# easyServo_easyEDA_PRO.net
KiCad netlist of a schematic drawn in EasyEDA Pro
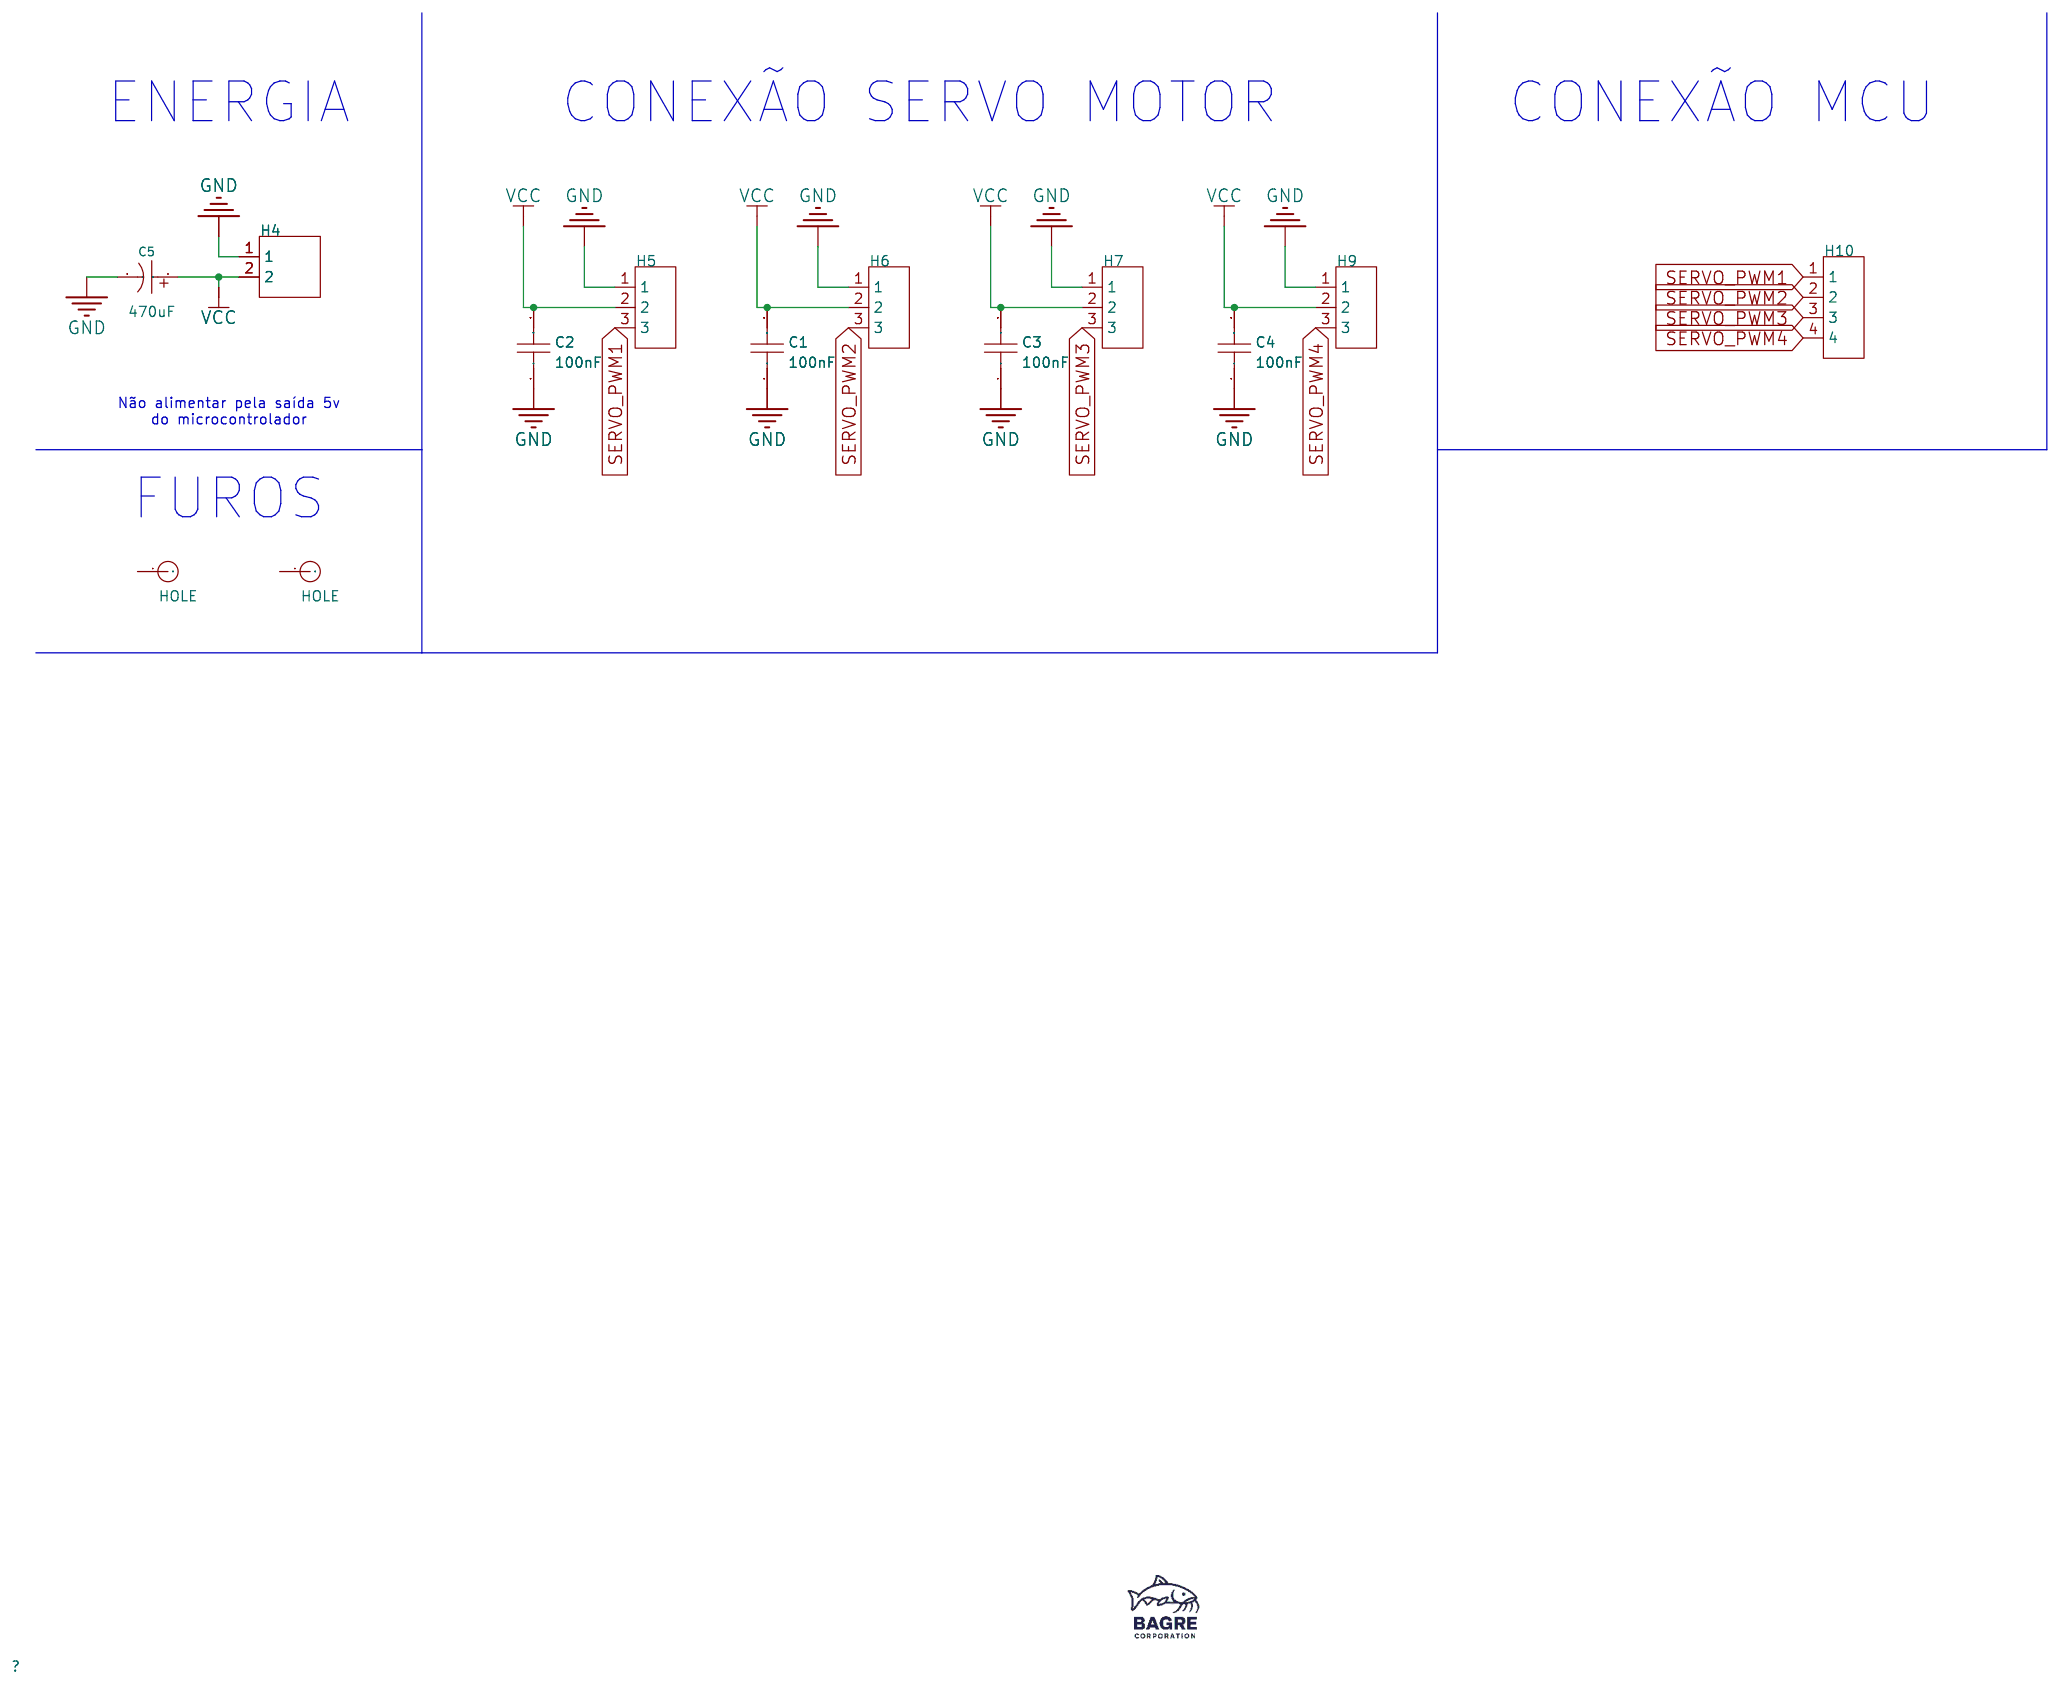
[diagram p0: schematic sheet]

(export (version "E")
  (design (tool "Eeschema 10.0.6"))
  (components
    (comp (ref "C1")
      (value "100nF")
      (footprint "easyedapro:C1206")
      (fields (field (name "Manufacturer Part") "CGJ5L3X7R2D104K160AA") (field (name "Manufacturer") "TDK"))
      (libsource (lib "easyedapro") (part "CGJ5L3X7R2D104K160AA_C3883443"))
    )
    (comp (ref "C2")
      (value "100nF")
      (footprint "easyedapro:C1206")
      (fields (field (name "Manufacturer Part") "CGJ5L3X7R2D104K160AA") (field (name "Manufacturer") "TDK"))
      (libsource (lib "easyedapro") (part "CGJ5L3X7R2D104K160AA_C3883443"))
    )
    (comp (ref "C3")
      (value "100nF")
      (footprint "easyedapro:C1206")
      (fields (field (name "Manufacturer Part") "CGJ5L3X7R2D104K160AA") (field (name "Manufacturer") "TDK"))
      (libsource (lib "easyedapro") (part "CGJ5L3X7R2D104K160AA_C3883443"))
    )
    (comp (ref "C4")
      (value "100nF")
      (footprint "easyedapro:C1206")
      (fields (field (name "Manufacturer Part") "CGJ5L3X7R2D104K160AA") (field (name "Manufacturer") "TDK"))
      (libsource (lib "easyedapro") (part "CGJ5L3X7R2D104K160AA_C3883443"))
    )
    (comp (ref "C5")
      (value "470uF")
      (footprint "easyedapro:CAP-TH_BD6.3-P2.50-D1.0-FD")
      (fields (field (name "Manufacturer Part") "ERR1CM471E14OT") (field (name "Manufacturer") "AISHI(艾华集团)"))
      (libsource (lib "easyedapro") (part "ERR1CM471E14OT"))
    )
    (comp (ref "H4")
      (value "~")
      (footprint "easyedapro:HDR-TH_2P-P2.54-V-M-1")
      (libsource (lib "easyedapro") (part "210S-1*2P L=11.6MMGold-plated black"))
    )
    (comp (ref "H5")
      (value "~")
      (footprint "easyedapro:HDR-TH_3P-P2.54-V-M")
      (libsource (lib "easyedapro") (part "PZ254V-11-03P_C2937625"))
    )
    (comp (ref "H6")
      (value "~")
      (footprint "easyedapro:HDR-TH_3P-P2.54-V-M")
      (libsource (lib "easyedapro") (part "PZ254V-11-03P_C2937625"))
    )
    (comp (ref "H7")
      (value "~")
      (footprint "easyedapro:HDR-TH_3P-P2.54-V-M")
      (libsource (lib "easyedapro") (part "PZ254V-11-03P_C2937625"))
    )
    (comp (ref "H9")
      (value "~")
      (footprint "easyedapro:HDR-TH_3P-P2.54-V-M")
      (libsource (lib "easyedapro") (part "PZ254V-11-03P_C2937625"))
    )
    (comp (ref "H10")
      (value "~")
      (footprint "easyedapro:HDR-TH_4P-P2.54-V-M")
      (libsource (lib "easyedapro") (part "PZ254V-11-04P"))
    )
    (comp (ref "J1")
      (value "HOLE")
      (footprint "easyedapro:M2 Mounting Hole - Conductive")
      (libsource (lib "easyedapro") (part "CONN THRU 1POS BOARD-WIRE 14-24AWG"))
    )
    (comp (ref "J2")
      (value "HOLE")
      (footprint "easyedapro:M2 Mounting Hole - Conductive")
      (libsource (lib "easyedapro") (part "CONN THRU 1POS BOARD-WIRE 14-24AWG"))
    )
  )
  (nets
    (net (code "1") (name "GND") (class "Default")
      (node (ref "C1") (pin "1") (pinfunction "1_1") (pintype "unspecified"))
      (node (ref "C2") (pin "1") (pinfunction "1_1") (pintype "unspecified"))
      (node (ref "C3") (pin "1") (pinfunction "1_1") (pintype "unspecified"))
      (node (ref "C4") (pin "1") (pinfunction "1_1") (pintype "unspecified"))
      (node (ref "C5") (pin "2") (pinfunction "2_2") (pintype "input"))
      (node (ref "H4") (pin "1") (pinfunction "1_1") (pintype "unspecified"))
      (node (ref "H5") (pin "1") (pinfunction "1_1") (pintype "unspecified"))
      (node (ref "H6") (pin "1") (pinfunction "1_1") (pintype "unspecified"))
      (node (ref "H7") (pin "1") (pinfunction "1_1") (pintype "unspecified"))
      (node (ref "H9") (pin "1") (pinfunction "1_1") (pintype "unspecified"))
    )
    (net (code "2") (name "SERVO_PWM1") (class "Default")
      (node (ref "H10") (pin "1") (pinfunction "1_1") (pintype "unspecified"))
      (node (ref "H5") (pin "3") (pinfunction "3_3") (pintype "unspecified"))
    )
    (net (code "3") (name "SERVO_PWM2") (class "Default")
      (node (ref "H10") (pin "2") (pinfunction "2_2") (pintype "unspecified"))
      (node (ref "H6") (pin "3") (pinfunction "3_3") (pintype "unspecified"))
    )
    (net (code "4") (name "SERVO_PWM3") (class "Default")
      (node (ref "H10") (pin "3") (pinfunction "3_3") (pintype "unspecified"))
      (node (ref "H7") (pin "3") (pinfunction "3_3") (pintype "unspecified"))
    )
    (net (code "5") (name "SERVO_PWM4") (class "Default")
      (node (ref "H10") (pin "4") (pinfunction "4_4") (pintype "unspecified"))
      (node (ref "H9") (pin "3") (pinfunction "3_3") (pintype "unspecified"))
    )
    (net (code "6") (name "VCC") (class "Default")
      (node (ref "C1") (pin "2") (pinfunction "2_2") (pintype "unspecified"))
      (node (ref "C2") (pin "2") (pinfunction "2_2") (pintype "unspecified"))
      (node (ref "C3") (pin "2") (pinfunction "2_2") (pintype "unspecified"))
      (node (ref "C4") (pin "2") (pinfunction "2_2") (pintype "unspecified"))
      (node (ref "C5") (pin "1") (pinfunction "1_1") (pintype "input"))
      (node (ref "H4") (pin "2") (pinfunction "2_2") (pintype "unspecified"))
      (node (ref "H5") (pin "2") (pinfunction "2_2") (pintype "unspecified"))
      (node (ref "H6") (pin "2") (pinfunction "2_2") (pintype "unspecified"))
      (node (ref "H7") (pin "2") (pinfunction "2_2") (pintype "unspecified"))
      (node (ref "H9") (pin "2") (pinfunction "2_2") (pintype "unspecified"))
    )
    (net (code "7") (name "unconnected-(J1-P1-Pad1)") (class "Default")
      (node (ref "J1") (pin "1") (pinfunction "P1_1") (pintype "unspecified"))
    )
    (net (code "8") (name "unconnected-(J2-P1-Pad1)") (class "Default")
      (node (ref "J2") (pin "1") (pinfunction "P1_1") (pintype "unspecified"))
    )
  )
)
